# PowerConverter.net
KiCad netlist of a schematic drawn in Altium Designer
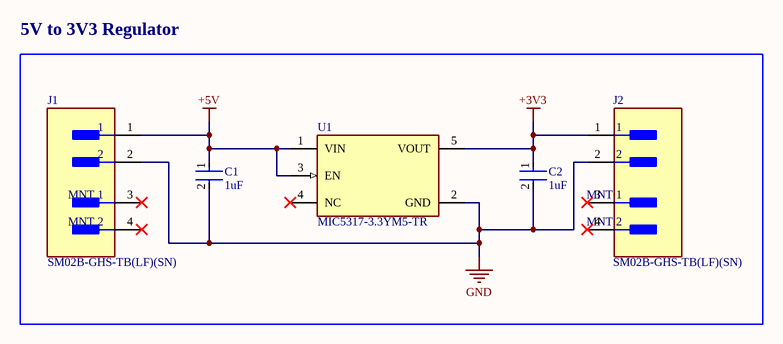
[diagram p0: PowerConverter.SchDoc]

(export (version "E")
  (design (tool "Eeschema 10.0.6"))
  (components
    (comp (ref "C1")
      (value "1uF")
      (footprint "FP-CC0805-0_85-MFG")
      (description "CAP CER 1UF 10V X7R 0805")
      (fields
        (field (name "MANUFACTURER") "Yageo")
        (field (name "OCTOPART") "https://octopart.com/cc0805kkx7r6bb105-yageo-42522859")
      )
      (libsource (lib "Altium Content Vault") (part "11868f565c42a9108669ba33697ecf6"))
    )
    (comp (ref "C2")
      (value "1uF")
      (footprint "FP-CC0805-0_85-MFG")
      (description "CAP CER 1UF 10V X7R 0805")
      (fields
        (field (name "MANUFACTURER") "Yageo")
        (field (name "OCTOPART") "https://octopart.com/cc0805kkx7r6bb105-yageo-42522859")
      )
      (libsource (lib "Altium Content Vault") (part "11868f565c42a9108669ba33697ecf6"))
    )
    (comp (ref "J1")
      (value "SM02B-GHS-TB(LF)(SN)")
      (footprint "FP-SM02B-GHS-TB_LF_SN-MFG")
      (description "CONN HEADER SMD R/A 2POS 1.25MM")
      (libsource (lib "Altium Content Vault") (part "56ec3178a87b3978bdc1b3682cd516a"))
    )
    (comp (ref "J2")
      (value "SM02B-GHS-TB(LF)(SN)")
      (footprint "FP-SM02B-GHS-TB_LF_SN-MFG")
      (description "CONN HEADER SMD R/A 2POS 1.25MM")
      (libsource (lib "") (part "56ec3178a87b3978bdc1b3682cd516a_1"))
    )
    (comp (ref "U1")
      (value "MIC5317-3.3YM5-TR")
      (footprint "FP-SOT23-5LD-PL-1-MFG")
      (description "IC REG LINEAR 3.3V 150MA SOT23-5")
      (libsource (lib "Altium Content Vault") (part "0a093dae7315cdc977fd108dde87457"))
    )
  )
  (nets
    (net (code "1") (name "+3V3") (class "Default")
      (node (ref "C2") (pin "1") (pinfunction "1_1") (pintype "passive"))
      (node (ref "J2") (pin "1") (pinfunction "1_1") (pintype "passive"))
      (node (ref "U1") (pin "5") (pinfunction "VOUT_5") (pintype "power_in"))
    )
    (net (code "2") (name "+5V") (class "Default")
      (node (ref "C1") (pin "1") (pinfunction "1_1") (pintype "passive"))
      (node (ref "J1") (pin "1") (pinfunction "1_1") (pintype "passive"))
      (node (ref "U1") (pin "1") (pinfunction "VIN_1") (pintype "power_in"))
      (node (ref "U1") (pin "3") (pinfunction "EN_3") (pintype "input"))
    )
    (net (code "3") (name "GND") (class "Default")
      (node (ref "C1") (pin "2") (pinfunction "2_2") (pintype "passive"))
      (node (ref "C2") (pin "2") (pinfunction "2_2") (pintype "passive"))
      (node (ref "J1") (pin "2") (pinfunction "2_2") (pintype "passive"))
      (node (ref "J2") (pin "2") (pinfunction "2_2") (pintype "passive"))
      (node (ref "U1") (pin "2") (pinfunction "GND_2") (pintype "power_in"))
    )
    (net (code "4") (name "unconnected-(J1-MNT_1-Pad3)") (class "Default")
      (node (ref "J1") (pin "3") (pinfunction "MNT_1_3") (pintype "passive+no_connect"))
    )
    (net (code "5") (name "unconnected-(J1-MNT_2-Pad4)") (class "Default")
      (node (ref "J1") (pin "4") (pinfunction "MNT_2_4") (pintype "passive+no_connect"))
    )
    (net (code "6") (name "unconnected-(J2-MNT_1-Pad3)") (class "Default")
      (node (ref "J2") (pin "3") (pinfunction "MNT_1_3") (pintype "passive+no_connect"))
    )
    (net (code "7") (name "unconnected-(J2-MNT_2-Pad4)") (class "Default")
      (node (ref "J2") (pin "4") (pinfunction "MNT_2_4") (pintype "passive+no_connect"))
    )
    (net (code "8") (name "unconnected-(U1-NC-Pad4)") (class "Default")
      (node (ref "U1") (pin "4") (pinfunction "NC_4") (pintype "passive+no_connect"))
    )
  )
)
